# BL653u.net
KiCad netlist of a schematic drawn in Altium Designer
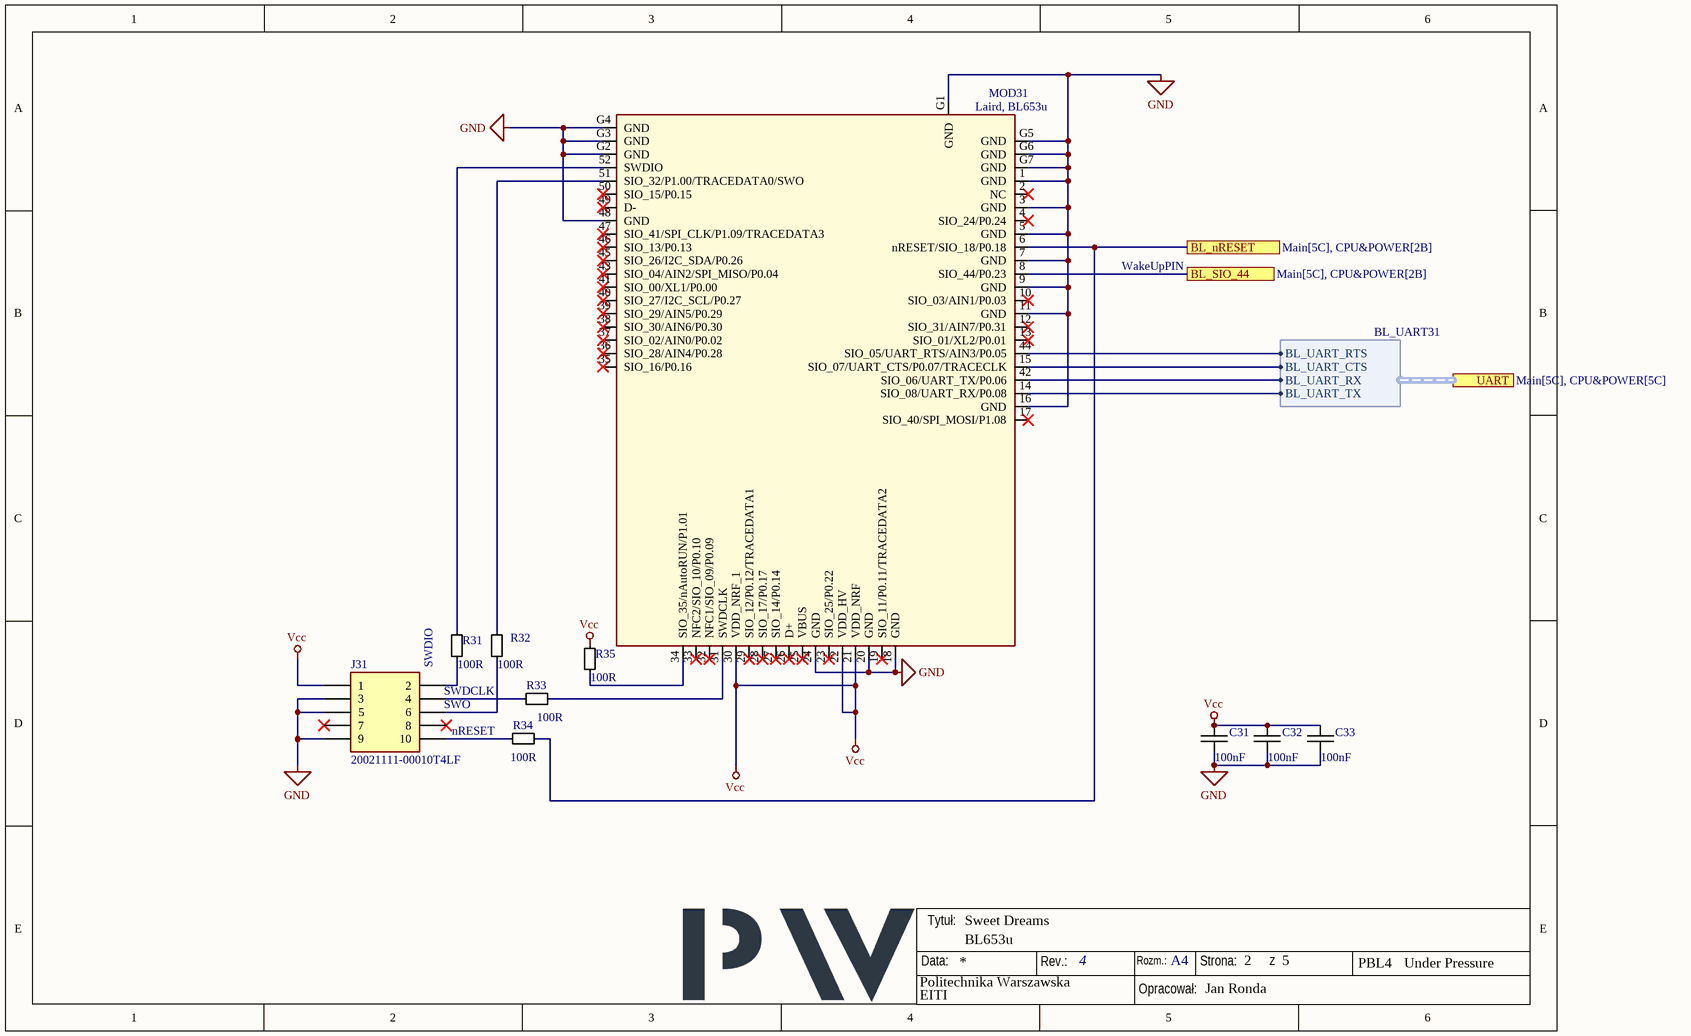
[diagram p0: BL653u.SchDoc]

(export (version "E")
  (design (tool "Eeschema 10.0.6"))
  (components
    (comp (ref "C31")
      (value "100nF")
      (footprint "0402_CAP")
      (description "Ceramic Capacitor")
      (fields (field (name "PARAMETER 1") "100nF"))
      (libsource (lib "Zad1") (part "Capacitor_1"))
    )
    (comp (ref "C32")
      (value "100nF")
      (footprint "0402_CAP")
      (description "Ceramic Capacitor")
      (fields (field (name "PARAMETER 1") "100nF"))
      (libsource (lib "Zad1") (part "Capacitor_1"))
    )
    (comp (ref "C33")
      (value "100nF")
      (footprint "0402_CAP")
      (description "Ceramic Capacitor")
      (fields (field (name "PARAMETER 1") "100nF"))
      (libsource (lib "Zad1") (part "Capacitor_1"))
    )
    (comp (ref "J31")
      (value "20021111-00010T4LF")
      (footprint "HDRV10W41P127_2X5_635X343X575P_m")
      (description "Connector")
      (fields (field (name "MOUSER PART NUMBER") "649-221111-00010T4LF"))
      (libsource (lib "SamacSys") (part "20021111-00010T4LF"))
    )
    (comp (ref "MOD31")
      (value "Laird, BL653u")
      (footprint "45300059C_m")
      (description "BL653µ Integrated Antenna module, 453-00059")
      (fields (field (name "MANUFACTURER PART NUMBER") "453-00059") (field (name "MANUFACTURER") "Laird"))
      (libsource (lib "BL653u_Integrated Antenna module 453-00059 SCH Symbol") (part "Laird, BL653u"))
    )
    (comp (ref "R31")
      (value "100R")
      (footprint "0402_RES")
      (fields (field (name "PARAMETER 1") "100R"))
      (libsource (lib "Zad1") (part "Resistor"))
    )
    (comp (ref "R32")
      (value "100R")
      (footprint "0402_RES")
      (fields (field (name "PARAMETER 1") "100R"))
      (libsource (lib "Zad1") (part "Resistor"))
    )
    (comp (ref "R33")
      (value "100R")
      (footprint "0402_RES")
      (fields (field (name "PARAMETER 1") "100R"))
      (libsource (lib "") (part "Resistor_2"))
    )
    (comp (ref "R34")
      (value "100R")
      (footprint "0402_RES")
      (description "Resistor")
      (fields (field (name "PARAMETER 1") "100R"))
      (libsource (lib "") (part "Resistor_2"))
    )
    (comp (ref "R35")
      (value "100R")
      (footprint "0402_RES")
      (fields (field (name "PARAMETER 1") "100R"))
      (libsource (lib "") (part "Resistor_1"))
    )
  )
  (nets
    (net (code "2") (name "/BL_SIO_44") (class "Default")
      (node (ref "MOD31") (pin "8") (pinfunction "SIO_44/P0.23_8") (pintype "passive"))
    )
    (net (code "3") (name "/BL_UART_CTS") (class "Default")
      (node (ref "MOD31") (pin "15") (pinfunction "SIO_07/UART_CTS/P0.07/TRACECLK_15") (pintype "passive"))
    )
    (net (code "4") (name "/BL_UART_RTS") (class "Default")
      (node (ref "MOD31") (pin "44") (pinfunction "SIO_05/UART_RTS/AIN3/P0.05_44") (pintype "passive"))
    )
    (net (code "5") (name "/BL_UART_RX") (class "Default")
      (node (ref "MOD31") (pin "42") (pinfunction "SIO_06/UART_TX/P0.06_42") (pintype "passive"))
    )
    (net (code "6") (name "/BL_UART_TX") (class "Default")
      (node (ref "MOD31") (pin "14") (pinfunction "SIO_08/UART_RX/P0.08_14") (pintype "passive"))
    )
    (net (code "7") (name "/BL_nRESET") (class "Default")
      (node (ref "MOD31") (pin "6") (pinfunction "nRESET/SIO_18/P0.18_6") (pintype "passive"))
      (node (ref "R34") (pin "1") (pinfunction "1_1") (pintype "passive"))
    )
    (net (code "9") (name "GND") (class "Default")
      (node (ref "C31") (pin "2") (pinfunction "0_2") (pintype "passive"))
      (node (ref "C32") (pin "2") (pinfunction "0_2") (pintype "passive"))
      (node (ref "C33") (pin "2") (pinfunction "0_2") (pintype "passive"))
      (node (ref "J31") (pin "3") (pinfunction "3_3") (pintype "passive"))
      (node (ref "J31") (pin "5") (pinfunction "5_5") (pintype "passive"))
      (node (ref "J31") (pin "9") (pinfunction "9_9") (pintype "passive"))
      (node (ref "MOD31") (pin "1") (pinfunction "GND_1") (pintype "passive"))
      (node (ref "MOD31") (pin "11") (pinfunction "GND_11") (pintype "passive"))
      (node (ref "MOD31") (pin "16") (pinfunction "GND_16") (pintype "passive"))
      (node (ref "MOD31") (pin "18") (pinfunction "GND_18") (pintype "passive"))
      (node (ref "MOD31") (pin "20") (pinfunction "GND_20") (pintype "passive"))
      (node (ref "MOD31") (pin "24") (pinfunction "GND_24") (pintype "passive"))
      (node (ref "MOD31") (pin "3") (pinfunction "GND_3") (pintype "passive"))
      (node (ref "MOD31") (pin "48") (pinfunction "GND_48") (pintype "passive"))
      (node (ref "MOD31") (pin "5") (pinfunction "GND_5") (pintype "passive"))
      (node (ref "MOD31") (pin "7") (pinfunction "GND_7") (pintype "passive"))
      (node (ref "MOD31") (pin "9") (pinfunction "GND_9") (pintype "passive"))
      (node (ref "MOD31") (pin "G1") (pinfunction "GND_G1") (pintype "passive"))
      (node (ref "MOD31") (pin "G2") (pinfunction "GND_G2") (pintype "passive"))
      (node (ref "MOD31") (pin "G3") (pinfunction "GND_G3") (pintype "passive"))
      (node (ref "MOD31") (pin "G4") (pinfunction "GND_G4") (pintype "passive"))
      (node (ref "MOD31") (pin "G5") (pinfunction "GND_G5") (pintype "passive"))
      (node (ref "MOD31") (pin "G6") (pinfunction "GND_G6") (pintype "passive"))
      (node (ref "MOD31") (pin "G7") (pinfunction "GND_G7") (pintype "passive"))
    )
    (net (code "10") (name "Net-(J31-Pad2)") (class "Default")
      (node (ref "J31") (pin "2") (pinfunction "2_2") (pintype "passive"))
      (node (ref "R31") (pin "1") (pinfunction "1_1") (pintype "passive"))
    )
    (net (code "11") (name "Net-(J31-Pad4)") (class "Default")
      (node (ref "J31") (pin "4") (pinfunction "4_4") (pintype "passive"))
      (node (ref "R33") (pin "2") (pinfunction "2_2") (pintype "passive"))
    )
    (net (code "12") (name "Net-(J31-Pad6)") (class "Default")
      (node (ref "J31") (pin "6") (pinfunction "6_6") (pintype "passive"))
      (node (ref "R32") (pin "1") (pinfunction "1_1") (pintype "passive"))
    )
    (net (code "13") (name "Net-(J31-Pad10)") (class "Default")
      (node (ref "J31") (pin "10") (pinfunction "10_10") (pintype "passive"))
      (node (ref "R34") (pin "2") (pinfunction "2_2") (pintype "passive"))
    )
    (net (code "14") (name "Net-(MOD31-SIO_32{slash}P1.00{slash}TRACEDATA0{slash}SWO)") (class "Default")
      (node (ref "MOD31") (pin "51") (pinfunction "SIO_32/P1.00/TRACEDATA0/SWO_51") (pintype "passive"))
      (node (ref "R32") (pin "2") (pinfunction "2_2") (pintype "passive"))
    )
    (net (code "15") (name "Net-(MOD31-SIO_35{slash}nAutoRUN{slash}P1.01)") (class "Default")
      (node (ref "MOD31") (pin "34") (pinfunction "SIO_35/nAutoRUN/P1.01_34") (pintype "passive"))
      (node (ref "R35") (pin "2") (pinfunction "2_2") (pintype "passive"))
    )
    (net (code "16") (name "Net-(MOD31-SWDCLK)") (class "Default")
      (node (ref "MOD31") (pin "31") (pinfunction "SWDCLK_31") (pintype "passive"))
      (node (ref "R33") (pin "1") (pinfunction "1_1") (pintype "passive"))
    )
    (net (code "17") (name "Net-(MOD31-SWDIO)") (class "Default")
      (node (ref "MOD31") (pin "52") (pinfunction "SWDIO_52") (pintype "passive"))
      (node (ref "R31") (pin "2") (pinfunction "2_2") (pintype "passive"))
    )
    (net (code "18") (name "Vcc") (class "Default")
      (node (ref "C31") (pin "1") (pinfunction "0_1") (pintype "passive"))
      (node (ref "C32") (pin "1") (pinfunction "0_1") (pintype "passive"))
      (node (ref "C33") (pin "1") (pinfunction "0_1") (pintype "passive"))
      (node (ref "J31") (pin "1") (pinfunction "1_1") (pintype "passive"))
      (node (ref "MOD31") (pin "21") (pinfunction "VDD_NRF_21") (pintype "passive"))
      (node (ref "MOD31") (pin "22") (pinfunction "VDD_HV_22") (pintype "passive"))
      (node (ref "MOD31") (pin "30") (pinfunction "VDD_NRF_1_30") (pintype "passive"))
      (node (ref "R35") (pin "1") (pinfunction "1_1") (pintype "passive"))
    )
    (net (code "19") (name "unconnected-(J31-Pad7)") (class "Default")
      (node (ref "J31") (pin "7") (pinfunction "7_7") (pintype "passive+no_connect"))
    )
    (net (code "20") (name "unconnected-(J31-Pad8)") (class "Default")
      (node (ref "J31") (pin "8") (pinfunction "8_8") (pintype "passive+no_connect"))
    )
    (net (code "21") (name "unconnected-(MOD31-D+-Pad26)") (class "Default")
      (node (ref "MOD31") (pin "26") (pinfunction "D+_26") (pintype "passive+no_connect"))
    )
    (net (code "22") (name "unconnected-(MOD31-D--Pad49)") (class "Default")
      (node (ref "MOD31") (pin "49") (pinfunction "D-_49") (pintype "passive+no_connect"))
    )
    (net (code "23") (name "unconnected-(MOD31-NC-Pad2)") (class "Default")
      (node (ref "MOD31") (pin "2") (pinfunction "NC_2") (pintype "passive+no_connect"))
    )
    (net (code "24") (name "unconnected-(MOD31-NFC1{slash}SIO_09{slash}P0.09-Pad32)") (class "Default")
      (node (ref "MOD31") (pin "32") (pinfunction "NFC1/SIO_09/P0.09_32") (pintype "passive+no_connect"))
    )
    (net (code "25") (name "unconnected-(MOD31-NFC2{slash}SIO_10{slash}P0.10-Pad33)") (class "Default")
      (node (ref "MOD31") (pin "33") (pinfunction "NFC2/SIO_10/P0.10_33") (pintype "passive+no_connect"))
    )
    (net (code "26") (name "unconnected-(MOD31-SIO_00{slash}XL1{slash}P0.00-Pad41)") (class "Default")
      (node (ref "MOD31") (pin "41") (pinfunction "SIO_00/XL1/P0.00_41") (pintype "passive+no_connect"))
    )
    (net (code "27") (name "unconnected-(MOD31-SIO_01{slash}XL2{slash}P0.01-Pad13)") (class "Default")
      (node (ref "MOD31") (pin "13") (pinfunction "SIO_01/XL2/P0.01_13") (pintype "passive+no_connect"))
    )
    (net (code "28") (name "unconnected-(MOD31-SIO_02{slash}AIN0{slash}P0.02-Pad37)") (class "Default")
      (node (ref "MOD31") (pin "37") (pinfunction "SIO_02/AIN0/P0.02_37") (pintype "passive+no_connect"))
    )
    (net (code "29") (name "unconnected-(MOD31-SIO_03{slash}AIN1{slash}P0.03-Pad10)") (class "Default")
      (node (ref "MOD31") (pin "10") (pinfunction "SIO_03/AIN1/P0.03_10") (pintype "passive+no_connect"))
    )
    (net (code "30") (name "unconnected-(MOD31-SIO_04{slash}AIN2{slash}SPI_MISO{slash}P0.04-Pad43)") (class "Default")
      (node (ref "MOD31") (pin "43") (pinfunction "SIO_04/AIN2/SPI_MISO/P0.04_43") (pintype "passive+no_connect"))
    )
    (net (code "31") (name "unconnected-(MOD31-SIO_11{slash}P0.11{slash}TRACEDATA2-Pad19)") (class "Default")
      (node (ref "MOD31") (pin "19") (pinfunction "SIO_11/P0.11/TRACEDATA2_19") (pintype "passive+no_connect"))
    )
    (net (code "32") (name "unconnected-(MOD31-SIO_12{slash}P0.12{slash}TRACEDATA1-Pad29)") (class "Default")
      (node (ref "MOD31") (pin "29") (pinfunction "SIO_12/P0.12/TRACEDATA1_29") (pintype "passive+no_connect"))
    )
    (net (code "33") (name "unconnected-(MOD31-SIO_13{slash}P0.13-Pad46)") (class "Default")
      (node (ref "MOD31") (pin "46") (pinfunction "SIO_13/P0.13_46") (pintype "passive+no_connect"))
    )
    (net (code "34") (name "unconnected-(MOD31-SIO_14{slash}P0.14-Pad27)") (class "Default")
      (node (ref "MOD31") (pin "27") (pinfunction "SIO_14/P0.14_27") (pintype "passive+no_connect"))
    )
    (net (code "35") (name "unconnected-(MOD31-SIO_15{slash}P0.15-Pad50)") (class "Default")
      (node (ref "MOD31") (pin "50") (pinfunction "SIO_15/P0.15_50") (pintype "passive+no_connect"))
    )
    (net (code "36") (name "unconnected-(MOD31-SIO_16{slash}P0.16-Pad35)") (class "Default")
      (node (ref "MOD31") (pin "35") (pinfunction "SIO_16/P0.16_35") (pintype "passive+no_connect"))
    )
    (net (code "37") (name "unconnected-(MOD31-SIO_17{slash}P0.17-Pad28)") (class "Default")
      (node (ref "MOD31") (pin "28") (pinfunction "SIO_17/P0.17_28") (pintype "passive+no_connect"))
    )
    (net (code "38") (name "unconnected-(MOD31-SIO_24{slash}P0.24-Pad4)") (class "Default")
      (node (ref "MOD31") (pin "4") (pinfunction "SIO_24/P0.24_4") (pintype "passive+no_connect"))
    )
    (net (code "39") (name "unconnected-(MOD31-SIO_25{slash}P0.22-Pad23)") (class "Default")
      (node (ref "MOD31") (pin "23") (pinfunction "SIO_25/P0.22_23") (pintype "passive+no_connect"))
    )
    (net (code "40") (name "unconnected-(MOD31-SIO_26{slash}I2C_SDA{slash}P0.26-Pad45)") (class "Default")
      (node (ref "MOD31") (pin "45") (pinfunction "SIO_26/I2C_SDA/P0.26_45") (pintype "passive+no_connect"))
    )
    (net (code "41") (name "unconnected-(MOD31-SIO_27{slash}I2C_SCL{slash}P0.27-Pad40)") (class "Default")
      (node (ref "MOD31") (pin "40") (pinfunction "SIO_27/I2C_SCL/P0.27_40") (pintype "passive+no_connect"))
    )
    (net (code "42") (name "unconnected-(MOD31-SIO_28{slash}AIN4{slash}P0.28-Pad36)") (class "Default")
      (node (ref "MOD31") (pin "36") (pinfunction "SIO_28/AIN4/P0.28_36") (pintype "passive+no_connect"))
    )
    (net (code "43") (name "unconnected-(MOD31-SIO_29{slash}AIN5{slash}P0.29-Pad39)") (class "Default")
      (node (ref "MOD31") (pin "39") (pinfunction "SIO_29/AIN5/P0.29_39") (pintype "passive+no_connect"))
    )
    (net (code "44") (name "unconnected-(MOD31-SIO_30{slash}AIN6{slash}P0.30-Pad38)") (class "Default")
      (node (ref "MOD31") (pin "38") (pinfunction "SIO_30/AIN6/P0.30_38") (pintype "passive+no_connect"))
    )
    (net (code "45") (name "unconnected-(MOD31-SIO_31{slash}AIN7{slash}P0.31-Pad12)") (class "Default")
      (node (ref "MOD31") (pin "12") (pinfunction "SIO_31/AIN7/P0.31_12") (pintype "passive+no_connect"))
    )
    (net (code "46") (name "unconnected-(MOD31-SIO_40{slash}SPI_MOSI{slash}P1.08-Pad17)") (class "Default")
      (node (ref "MOD31") (pin "17") (pinfunction "SIO_40/SPI_MOSI/P1.08_17") (pintype "passive+no_connect"))
    )
    (net (code "47") (name "unconnected-(MOD31-SIO_41{slash}SPI_CLK{slash}P1.09{slash}TRACEDATA3-Pad47)") (class "Default")
      (node (ref "MOD31") (pin "47") (pinfunction "SIO_41/SPI_CLK/P1.09/TRACEDATA3_47") (pintype "passive+no_connect"))
    )
    (net (code "48") (name "unconnected-(MOD31-VBUS-Pad25)") (class "Default")
      (node (ref "MOD31") (pin "25") (pinfunction "VBUS_25") (pintype "passive+no_connect"))
    )
  )
)
